# M66BoardSCH.net
KiCad netlist of a schematic drawn in Altium Designer
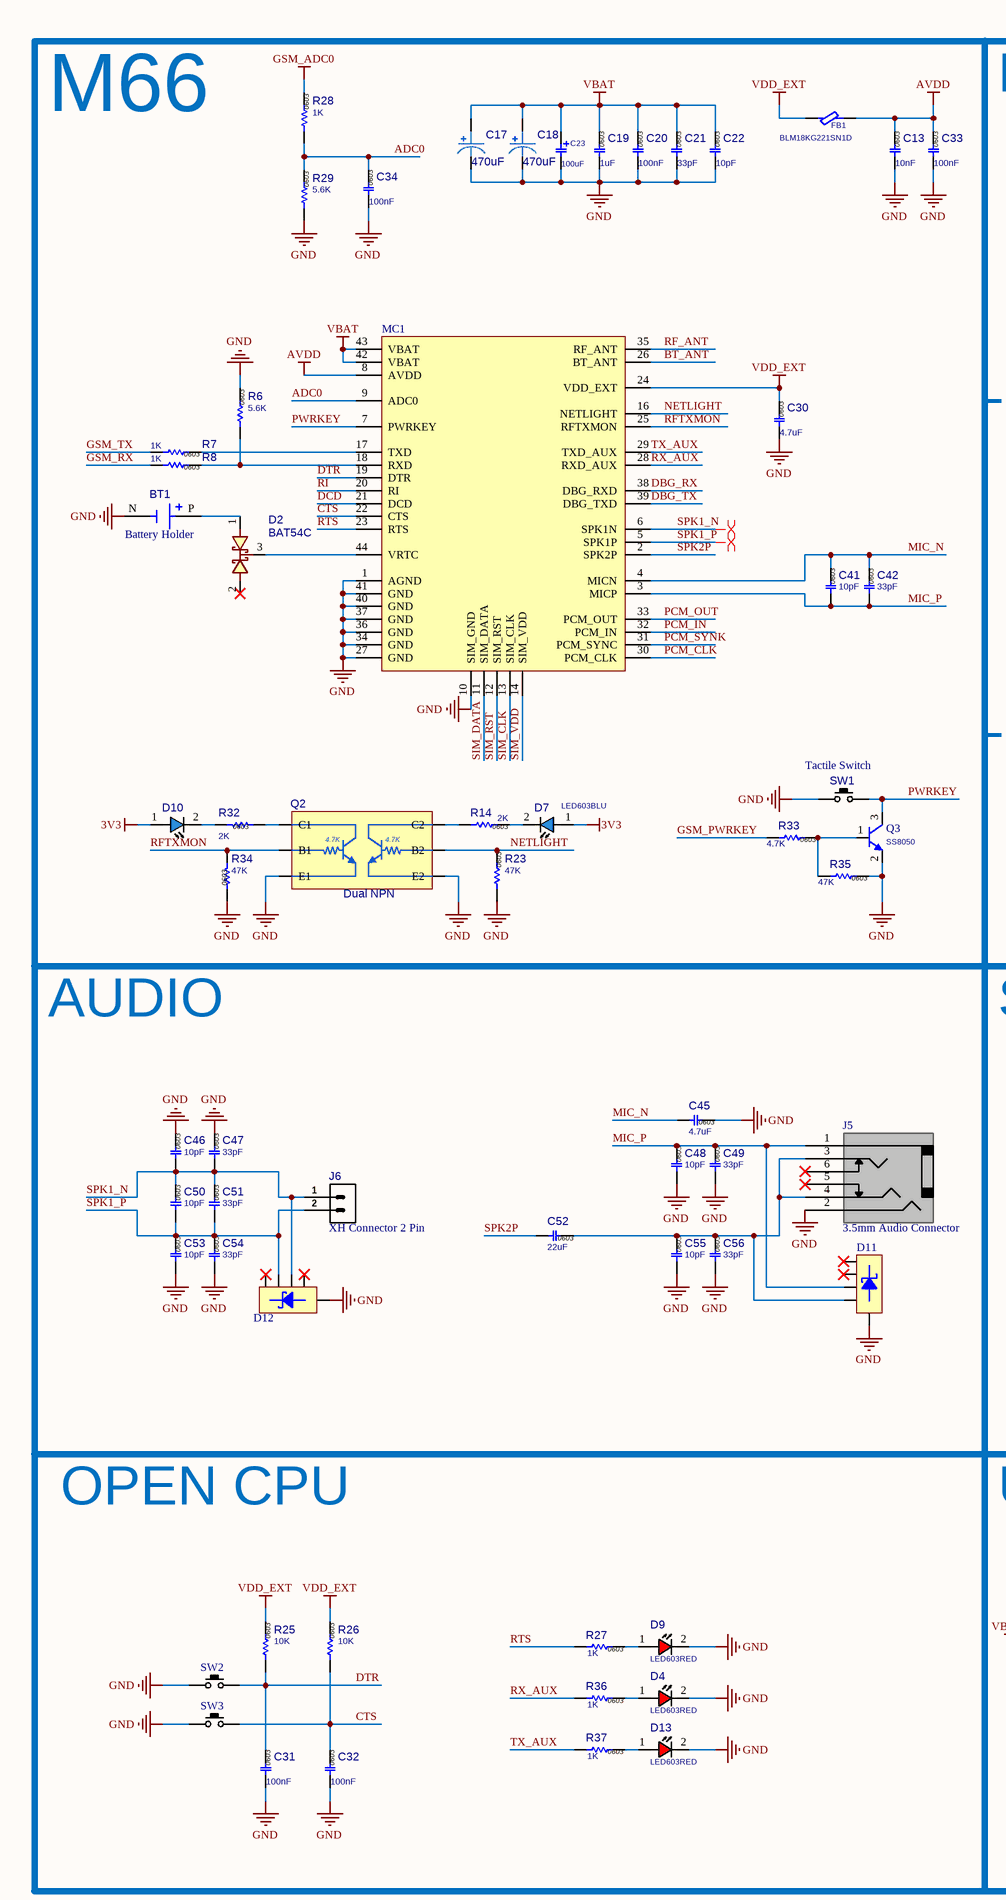
[diagram p0: M66BoardSCH.SchDoc, left]
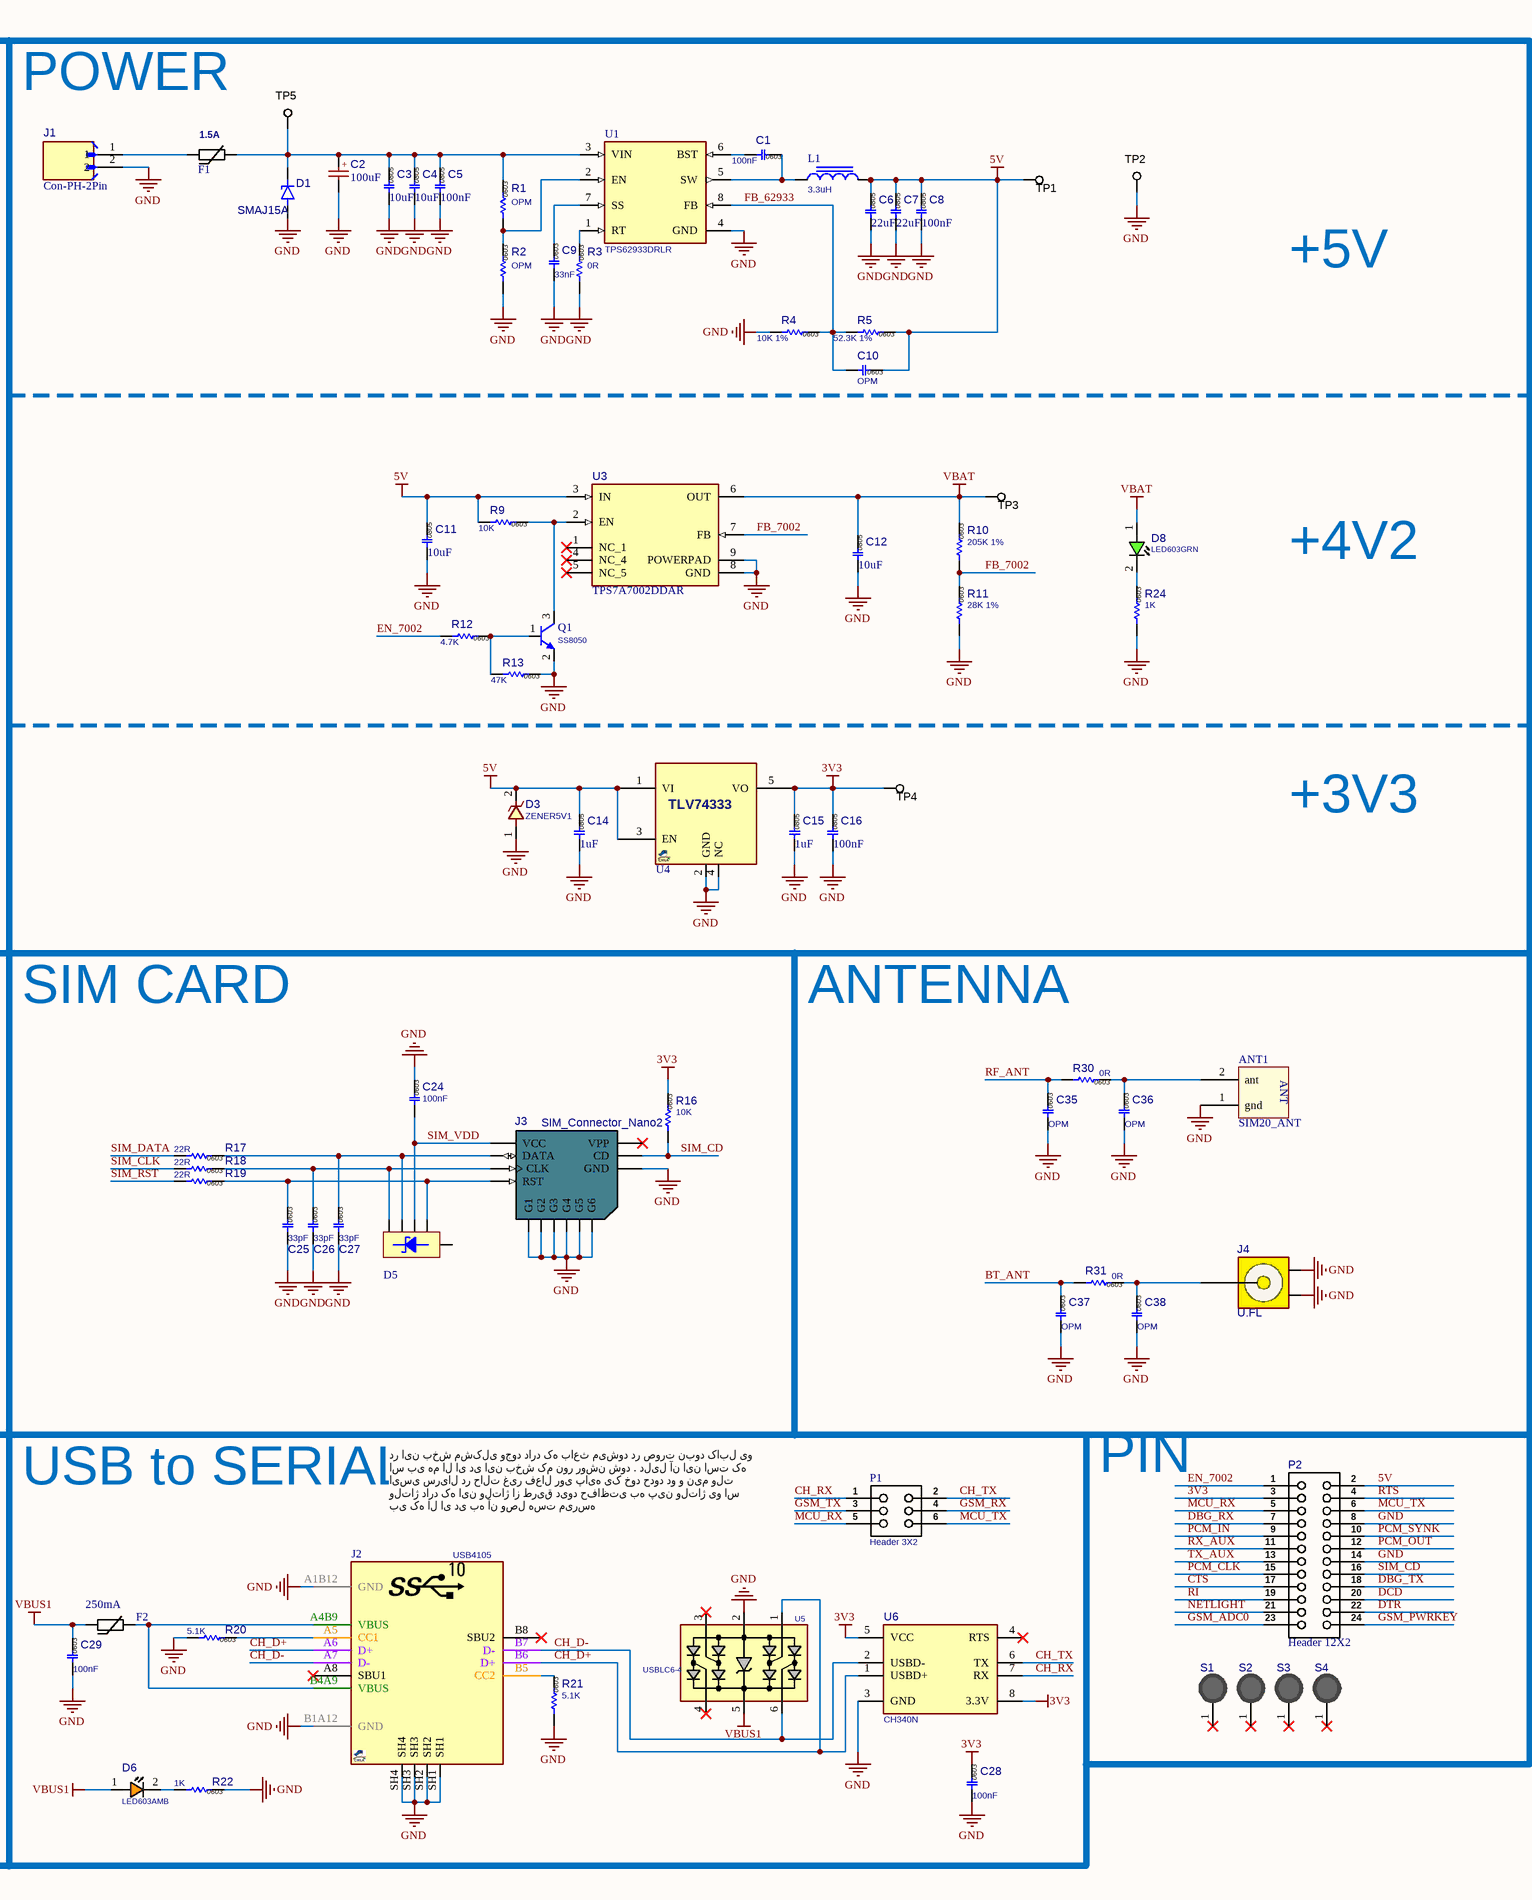
[diagram p1: M66BoardSCH.SchDoc, right]

(export (version "E")
  (design (tool "Eeschema 10.0.6"))
  (components
    (comp (ref "ANT1")
      (value "SIM20_ANT")
      (footprint "MY_SIM20_ANT")
      (description "ANT")
      (libsource (lib "AMINLIB") (part "SIM20_ANT"))
    )
    (comp (ref "BT1")
      (value "Battery Holder")
      (footprint "BS-06-B4AK008")
      (libsource (lib "Mehrdad") (part "Battery Holder"))
    )
    (comp (ref "C1")
      (value "100nF")
      (footprint "Cap SMD 0603")
      (libsource (lib "Mehrdad") (part "Cap SMD 0603"))
    )
    (comp (ref "C2")
      (value "100uF")
      (footprint "Cap SMD 6.3x5.4mm")
      (description "SMD Aluminum Electrolytic Capacitor")
      (fields
        (field (name "VOLTAGE") "12v")
        (field (name "TOLERANCE") "5%")
        (field (name "PUBLISHER") "Majid Derhambakhsh")
      )
      (libsource (lib "mBedLab Altium Library (2024-04-20)") (part "CAP Electrolytic SMD"))
    )
    (comp (ref "C3")
      (value "10uF")
      (footprint "Cap SMD 0805")
      (libsource (lib "Mehrdad") (part "Cap SMD 0805"))
    )
    (comp (ref "C4")
      (value "10uF")
      (footprint "Cap SMD 0805")
      (libsource (lib "Mehrdad") (part "Cap SMD 0805"))
    )
    (comp (ref "C5")
      (value "100nF")
      (footprint "Cap SMD 0805")
      (libsource (lib "Mehrdad") (part "Cap SMD 0805"))
    )
    (comp (ref "C6")
      (value "22uF")
      (footprint "Cap SMD 0805")
      (libsource (lib "Mehrdad") (part "Cap SMD 0805"))
    )
    (comp (ref "C7")
      (value "22uF")
      (footprint "Cap SMD 0805")
      (libsource (lib "Mehrdad") (part "Cap SMD 0805"))
    )
    (comp (ref "C8")
      (value "100nF")
      (footprint "Cap SMD 0805")
      (libsource (lib "Mehrdad") (part "Cap SMD 0805"))
    )
    (comp (ref "C9")
      (value "33nF")
      (footprint "Cap SMD 0603")
      (libsource (lib "Mehrdad") (part "Cap SMD 0603"))
    )
    (comp (ref "C10")
      (value "OPM")
      (footprint "Cap SMD 0603")
      (libsource (lib "Mehrdad") (part "Cap SMD 0603"))
    )
    (comp (ref "C11")
      (value "10uF")
      (footprint "Cap SMD 0805")
      (libsource (lib "Mehrdad") (part "Cap SMD 0805"))
    )
    (comp (ref "C12")
      (value "10uF")
      (footprint "Cap SMD 0805")
      (libsource (lib "Mehrdad") (part "Cap SMD 0805"))
    )
    (comp (ref "C13")
      (value "10nF")
      (footprint "Cap SMD 0603")
      (libsource (lib "Mehrdad") (part "Cap SMD 0603"))
    )
    (comp (ref "C14")
      (value "1uF")
      (footprint "Cap SMD 0805")
      (libsource (lib "Mehrdad") (part "Cap SMD 0805"))
    )
    (comp (ref "C15")
      (value "1uF")
      (footprint "Cap SMD 0805")
      (libsource (lib "Mehrdad") (part "Cap SMD 0805"))
    )
    (comp (ref "C16")
      (value "100nF")
      (footprint "Cap SMD 0805")
      (libsource (lib "Mehrdad") (part "Cap SMD 0805"))
    )
    (comp (ref "C17")
      (value "470uF")
      (footprint "Solid Capacitor 6.3x8mm")
      (description "Solid Polymer Electrolytic Capacitor")
      (libsource (lib "Mehrdad") (part "CAP Solid"))
    )
    (comp (ref "C18")
      (value "470uF")
      (footprint "Solid Capacitor 6.3x8mm")
      (description "Solid Polymer Electrolytic Capacitor")
      (libsource (lib "Mehrdad") (part "CAP Solid"))
    )
    (comp (ref "C19")
      (value "1uF")
      (footprint "Cap SMD 0603")
      (libsource (lib "Mehrdad") (part "Cap SMD 0603"))
    )
    (comp (ref "C20")
      (value "100nF")
      (footprint "Cap SMD 0603")
      (libsource (lib "Mehrdad") (part "Cap SMD 0603"))
    )
    (comp (ref "C21")
      (value "33pF")
      (footprint "Cap SMD 0603")
      (libsource (lib "Mehrdad") (part "Cap SMD 0603"))
    )
    (comp (ref "C22")
      (value "10pF")
      (footprint "Cap SMD 0603")
      (libsource (lib "Mehrdad") (part "Cap SMD 0603"))
    )
    (comp (ref "C23")
      (value "100uF")
      (footprint "C_TN_3528_BLK")
      (description "CAP, SMD, TAN")
      (fields (field (name "MANF") "VISHAY") (field (name "MANF_P#") "T55A106M6R3C0300"))
      (libsource (lib "AVR_RCS") (part "CAP_SMD_TAN_4"))
    )
    (comp (ref "C24")
      (value "100nF")
      (footprint "Cap SMD 0603")
      (libsource (lib "Mehrdad") (part "Cap SMD 0603"))
    )
    (comp (ref "C25")
      (value "33pF")
      (footprint "Cap SMD 0603")
      (libsource (lib "Mehrdad") (part "Cap SMD 0603"))
    )
    (comp (ref "C26")
      (value "33pF")
      (footprint "Cap SMD 0603")
      (libsource (lib "Mehrdad") (part "Cap SMD 0603"))
    )
    (comp (ref "C27")
      (value "33pF")
      (footprint "Cap SMD 0603")
      (libsource (lib "Mehrdad") (part "Cap SMD 0603"))
    )
    (comp (ref "C28")
      (value "100nF")
      (footprint "Cap SMD 0603")
      (libsource (lib "Mehrdad") (part "Cap SMD 0603"))
    )
    (comp (ref "C29")
      (value "100nF")
      (footprint "Cap SMD 0603")
      (libsource (lib "Mehrdad") (part "Cap SMD 0603"))
    )
    (comp (ref "C30")
      (value "4.7uF")
      (footprint "Cap SMD 0603")
      (libsource (lib "Mehrdad") (part "Cap SMD 0603"))
    )
    (comp (ref "C31")
      (value "100nF")
      (footprint "Cap SMD 0603")
      (libsource (lib "Mehrdad") (part "Cap SMD 0603"))
    )
    (comp (ref "C32")
      (value "100nF")
      (footprint "Cap SMD 0603")
      (libsource (lib "Mehrdad") (part "Cap SMD 0603"))
    )
    (comp (ref "C33")
      (value "100nF")
      (footprint "Cap SMD 0603")
      (libsource (lib "Mehrdad") (part "Cap SMD 0603"))
    )
    (comp (ref "C34")
      (value "100nF")
      (footprint "Cap SMD 0603")
      (libsource (lib "Mehrdad") (part "Cap SMD 0603"))
    )
    (comp (ref "C35")
      (value "OPM")
      (footprint "Cap SMD 0603")
      (libsource (lib "Mehrdad") (part "Cap SMD 0603"))
    )
    (comp (ref "C36")
      (value "OPM")
      (footprint "Cap SMD 0603")
      (libsource (lib "Mehrdad") (part "Cap SMD 0603"))
    )
    (comp (ref "C37")
      (value "OPM")
      (footprint "Cap SMD 0603")
      (libsource (lib "Mehrdad") (part "Cap SMD 0603"))
    )
    (comp (ref "C38")
      (value "OPM")
      (footprint "Cap SMD 0603")
      (libsource (lib "Mehrdad") (part "Cap SMD 0603"))
    )
    (comp (ref "C41")
      (value "10pF")
      (footprint "Cap SMD 0603")
      (libsource (lib "Mehrdad") (part "Cap SMD 0603"))
    )
    (comp (ref "C42")
      (value "33pF")
      (footprint "Cap SMD 0603")
      (libsource (lib "Mehrdad") (part "Cap SMD 0603"))
    )
    (comp (ref "C45")
      (value "4.7uF")
      (footprint "Cap SMD 0603")
      (libsource (lib "Mehrdad") (part "Cap SMD 0603"))
    )
    (comp (ref "C46")
      (value "10pF")
      (footprint "Cap SMD 0603")
      (libsource (lib "Mehrdad") (part "Cap SMD 0603"))
    )
    (comp (ref "C47")
      (value "33pF")
      (footprint "Cap SMD 0603")
      (libsource (lib "Mehrdad") (part "Cap SMD 0603"))
    )
    (comp (ref "C48")
      (value "10pF")
      (footprint "Cap SMD 0603")
      (libsource (lib "Mehrdad") (part "Cap SMD 0603"))
    )
    (comp (ref "C49")
      (value "33pF")
      (footprint "Cap SMD 0603")
      (libsource (lib "Mehrdad") (part "Cap SMD 0603"))
    )
    (comp (ref "C50")
      (value "10pF")
      (footprint "Cap SMD 0603")
      (libsource (lib "Mehrdad") (part "Cap SMD 0603"))
    )
    (comp (ref "C51")
      (value "33pF")
      (footprint "Cap SMD 0603")
      (libsource (lib "Mehrdad") (part "Cap SMD 0603"))
    )
    (comp (ref "C52")
      (value "22uF")
      (footprint "Cap SMD 0603")
      (libsource (lib "Mehrdad") (part "Cap SMD 0603"))
    )
    (comp (ref "C53")
      (value "10pF")
      (footprint "Cap SMD 0603")
      (libsource (lib "Mehrdad") (part "Cap SMD 0603"))
    )
    (comp (ref "C54")
      (value "33pF")
      (footprint "Cap SMD 0603")
      (libsource (lib "Mehrdad") (part "Cap SMD 0603"))
    )
    (comp (ref "C55")
      (value "10pF")
      (footprint "Cap SMD 0603")
      (libsource (lib "Mehrdad") (part "Cap SMD 0603"))
    )
    (comp (ref "C56")
      (value "33pF")
      (footprint "Cap SMD 0603")
      (libsource (lib "Mehrdad") (part "Cap SMD 0603"))
    )
    (comp (ref "D1")
      (value "SMAJ15A")
      (footprint "SMAJ15A")
      (description "TVS Diode Uni-directional 15V SMA  BR Voltage : 16.7V  Clamping Volatage : 24.4V")
      (libsource (lib "Mehrdad") (part "SMAJ15A"))
    )
    (comp (ref "D2")
      (value "BAT54C")
      (footprint "SOT23_3")
      (description "DIODE, SCHOTTKY, DUAL, 30V, 0.2A")
      (fields (field (name "MANF") "Diodes") (field (name "MANF_P#") "BAT54C-7-F"))
      (libsource (lib "diode") (part "DIODE_SMD_SCHOTTKY_BAT54C"))
    )
    (comp (ref "D3")
      (value "ZENER5V1")
      (footprint "D_SOD123W")
      (description "DIODE, ZENER, 1W, 5.1V")
      (fields (field (name "MANF") "Diodes") (field (name "MANF_P#") "BZT52HC5V1WF-7"))
      (libsource (lib "AVR_RCS") (part "DIODE_SMD_ZENER_BZT52HC5V1"))
    )
    (comp (ref "D4")
      (value "LED603RED")
      (footprint "LED0603RED")
      (description "LED, SMD, 0603, RED")
      (fields (field (name "MANF") "MANF") (field (name "MANF_P#") "MANF_PART#"))
      (libsource (lib "led(diode)") (part "LED_SMD_0603_RED"))
    )
    (comp (ref "D5")
      (value "SMF-05")
      (footprint "SC70-5_N")
      (description "TVS Diode Array")
      (fields (field (name "VALIDATION") "Valid"))
      (libsource (lib "") (part "Semi_Diod_TVS_SMF05_1"))
    )
    (comp (ref "D6")
      (value "LED603AMB")
      (footprint "LED0603AMB")
      (description "LED, SMD, 0603, AMBER, 606nm")
      (fields (field (name "MANF") "OSRAM") (field (name "MANF_P#") "L29K-H2K1-24-Z"))
      (libsource (lib "led(diode)") (part "LED_SMD_0603_AMB"))
    )
    (comp (ref "D7")
      (value "LED603BLU")
      (footprint "LED0603BLU")
      (description "LED, SMD, 0603, BLUE")
      (fields (field (name "MANF") "MANF") (field (name "MANF_P#") "MANF_PART#"))
      (libsource (lib "led(diode)") (part "LED_SMD_0603_BLU"))
    )
    (comp (ref "D8")
      (value "LED603GRN")
      (footprint "LED0603GRN")
      (description "LED, SMD, 0603, GREEN")
      (fields (field (name "MANF") "Kingbright") (field (name "MANF_P#") "APT1608SGC"))
      (libsource (lib "led(diode)") (part "LED_SMD_0603_GRN"))
    )
    (comp (ref "D9")
      (value "LED603RED")
      (footprint "LED0603RED")
      (description "LED, SMD, 0603, RED")
      (fields (field (name "MANF") "MANF") (field (name "MANF_P#") "MANF_PART#"))
      (libsource (lib "led(diode)") (part "LED_SMD_0603_RED"))
    )
    (comp (ref "D10")
      (value "LED603BLU")
      (footprint "LED0603BLU")
      (description "LED, SMD, 0603, BLUE")
      (fields (field (name "MANF") "MANF") (field (name "MANF_P#") "MANF_PART#"))
      (libsource (lib "led(diode)") (part "LED_SMD_0603_BLU"))
    )
    (comp (ref "D11")
      (value "SMF-05")
      (footprint "SC70-5_N")
      (description "TVS Diode Array")
      (fields (field (name "VALIDATION") "Valid"))
      (libsource (lib "aKaReZa") (part "Semi_Diod_TVS_SMF05"))
    )
    (comp (ref "D12")
      (value "SMF-05")
      (footprint "SC70-5_N")
      (description "TVS Diode Array")
      (fields (field (name "VALIDATION") "Valid"))
      (libsource (lib "") (part "Semi_Diod_TVS_SMF05_1"))
    )
    (comp (ref "D13")
      (value "LED603RED")
      (footprint "LED0603RED")
      (description "LED, SMD, 0603, RED")
      (fields (field (name "MANF") "MANF") (field (name "MANF_P#") "MANF_PART#"))
      (libsource (lib "led(diode)") (part "LED_SMD_0603_RED"))
    )
    (comp (ref "F1")
      (value "1.5A")
      (footprint "FUSE1206 (3216)")
      (fields (field (name "PUBLISHER") "Majid Derhambakhsh"))
      (libsource (lib "mBedLab Altium Library (2024-04-20)") (part "PPTC Resettable Fuses"))
    )
    (comp (ref "F2")
      (value "250mA")
      (footprint "FUSE0603 (1608)")
      (fields (field (name "PUBLISHER") "Majid Derhambakhsh"))
      (libsource (lib "mBedLab Altium Library (2024-04-20)") (part "PPTC Resettable Fuses"))
    )
    (comp (ref "FB1")
      (value "BLM18KG221SN1D")
      (footprint "L0603")
      (description "FERRITE_Bead, 0603, 2A, 50mOhm, 120@100MHz")
      (fields (field (name "MANF") "MURATA") (field (name "MANF_P#") "BLM18PG121SN1D"))
      (libsource (lib "emi_filter") (part "FBEAD_SMD_BLM18PG121"))
    )
    (comp (ref "J1")
      (value "Con-PH-2Pin")
      (footprint "Con-PH-2Pin-RA")
      (description "Connector Header Through Hole 2 position 0.079 (2.00mm)")
      (libsource (lib "Mehrdad") (part "Con-PH-2Pin"))
    )
    (comp (ref "J2")
      (value "USB4105")
      (footprint "USBC_SMD_16_USB4105")
      (description "CONN, USB, Type C, USB 2.0, Right-Angle, SMD")
      (fields (field (name "MANF") "GCT") (field (name "MANF_P#") "USB4105-GF-A"))
      (libsource (lib "conn_usbc") (part "CONN_USBC_SMD_16_USB4105"))
    )
    (comp (ref "J3")
      (value "SIM_Connector_Nano2")
      (footprint "SIM_Connector_Nano2")
      (description "Nano Sim Card 6P SMT-Card Detection")
      (libsource (lib "Mehrdad") (part "SIM_Connector_Nano2"))
    )
    (comp (ref "J4")
      (value "U.FL")
      (footprint "UFL")
      (description "CONN, RF, U.FL, STRAIGHT, Ultra Miniature Coaxial")
      (fields
        (field (name "MANF_P#") "CONUFL001-SMD, U.FL-R-SMT-1(10), 128-0711-201")
        (field (name "MANF") "Linx, Hirose, Cinch")
      )
      (libsource (lib "conn_rf") (part "CONN_RF_UFL"))
    )
    (comp (ref "J5")
      (value "3.5mm Audio Connector")
      (footprint "PJ311D")
      (libsource (lib "Mehrdad") (part "PJ311D"))
    )
    (comp (ref "J6")
      (value "XH Connector 2 Pin")
      (footprint "XH 2 Pin - 2.5mm")
      (description "XH, 2-Pin")
      (fields (field (name "PUBLISHER") "Majid Derhambakhsh"))
      (libsource (lib "mBedLab Altium Library (2024-04-20)") (part "XH 2"))
    )
    (comp (ref "L1")
      (value "3.3uH")
      (footprint "SMD Inductor 3")
      (description "1008 (2520 metric) Part Number : DFE252012F-4R7M=P2")
      (libsource (lib "Mehrdad") (part "SMD Inductor 3"))
    )
    (comp (ref "MC1")
      (value "M66")
      (footprint "m66")
      (description "Quectel GSM/GPRS Module")
      (fields (field (name "VALIDATION") "Valid"))
      (libsource (lib "AVR_RCS") (part "ModSen_Com_M66"))
    )
    (comp (ref "P1")
      (value "Header 3X2")
      (footprint "HDR 2X3 Male Top")
      (description "Header, 3-Pin, Dual row")
      (fields (field (name "PUBLISHER") "Majid Derhambakhsh"))
      (libsource (lib "mBedLab Altium Library (2024-04-20)") (part "Header 3X2"))
    )
    (comp (ref "P2")
      (value "Header 12X2")
      (footprint "HDR 2X12 Male Top")
      (description "Header, 12-Pin, Dual row")
      (fields (field (name "PUBLISHER") "Majid Derhambakhsh"))
      (libsource (lib "mBedLab Altium Library (2024-04-20)") (part "Header 12X2"))
    )
    (comp (ref "Q1")
      (value "SS8050")
      (footprint "SOT23_3")
      (description "BJT, NPN, 25v, 1.5A, SMD, SOT23")
      (fields (field (name "MANF") "GALAXY"))
      (libsource (lib "transistor_bjt") (part "NPN_SS8050_SOT23"))
    )
    (comp (ref "Q2")
      (value "Dual NPN")
      (footprint "PUMH7")
      (description "2 NPN 50V 100mA Transistors (Resistor-Equipped R1 = 4.7kΩ) SOT-363")
      (libsource (lib "Mehrdad") (part "PUMH7"))
    )
    (comp (ref "Q3")
      (value "SS8050")
      (footprint "SOT23_3")
      (description "BJT, NPN, 25v, 1.5A, SMD, SOT23")
      (fields (field (name "MANF") "GALAXY"))
      (libsource (lib "transistor_bjt") (part "NPN_SS8050_SOT23"))
    )
    (comp (ref "R1")
      (value "OPM")
      (footprint "Res SMD 0603")
      (libsource (lib "Mehrdad") (part "Res SMD 0603"))
    )
    (comp (ref "R2")
      (value "OPM")
      (footprint "Res SMD 0603")
      (libsource (lib "Mehrdad") (part "Res SMD 0603"))
    )
    (comp (ref "R3")
      (value "0R")
      (footprint "Res SMD 0603")
      (libsource (lib "Mehrdad") (part "Res SMD 0603"))
    )
    (comp (ref "R4")
      (value "10K 1%")
      (footprint "Res SMD 0603")
      (libsource (lib "Mehrdad") (part "Res SMD 0603"))
    )
    (comp (ref "R5")
      (value "52.3K 1%")
      (footprint "Res SMD 0603")
      (libsource (lib "Mehrdad") (part "Res SMD 0603"))
    )
    (comp (ref "R6")
      (value "5.6K")
      (footprint "Res SMD 0603")
      (libsource (lib "Mehrdad") (part "Res SMD 0603"))
    )
    (comp (ref "R7")
      (value "1K")
      (footprint "Res SMD 0603")
      (libsource (lib "Mehrdad") (part "Res SMD 0603"))
    )
    (comp (ref "R8")
      (value "1K")
      (footprint "Res SMD 0603")
      (libsource (lib "Mehrdad") (part "Res SMD 0603"))
    )
    (comp (ref "R9")
      (value "10K")
      (footprint "Res SMD 0603")
      (libsource (lib "Mehrdad") (part "Res SMD 0603"))
    )
    (comp (ref "R10")
      (value "205K 1%")
      (footprint "Res SMD 0603")
      (libsource (lib "Mehrdad") (part "Res SMD 0603"))
    )
    (comp (ref "R11")
      (value "28K 1%")
      (footprint "Res SMD 0603")
      (libsource (lib "Mehrdad") (part "Res SMD 0603"))
    )
    (comp (ref "R12")
      (value "4.7K")
      (footprint "Res SMD 0603")
      (libsource (lib "Mehrdad") (part "Res SMD 0603"))
    )
    (comp (ref "R13")
      (value "47K")
      (footprint "Res SMD 0603")
      (libsource (lib "Mehrdad") (part "Res SMD 0603"))
    )
    (comp (ref "R14")
      (value "2K")
      (footprint "Res SMD 0603")
      (libsource (lib "Mehrdad") (part "Res SMD 0603"))
    )
    (comp (ref "R16")
      (value "10K")
      (footprint "Res SMD 0603")
      (libsource (lib "Mehrdad") (part "Res SMD 0603"))
    )
    (comp (ref "R17")
      (value "22R")
      (footprint "Res SMD 0603")
      (libsource (lib "Mehrdad") (part "Res SMD 0603"))
    )
    (comp (ref "R18")
      (value "22R")
      (footprint "Res SMD 0603")
      (libsource (lib "Mehrdad") (part "Res SMD 0603"))
    )
    (comp (ref "R19")
      (value "22R")
      (footprint "Res SMD 0603")
      (libsource (lib "Mehrdad") (part "Res SMD 0603"))
    )
    (comp (ref "R20")
      (value "5.1K")
      (footprint "Res SMD 0603")
      (libsource (lib "Mehrdad") (part "Res SMD 0603"))
    )
    (comp (ref "R21")
      (value "5.1K")
      (footprint "Res SMD 0603")
      (libsource (lib "Mehrdad") (part "Res SMD 0603"))
    )
    (comp (ref "R22")
      (value "1K")
      (footprint "Res SMD 0603")
      (libsource (lib "Mehrdad") (part "Res SMD 0603"))
    )
    (comp (ref "R23")
      (value "47K")
      (footprint "Res SMD 0603")
      (libsource (lib "Mehrdad") (part "Res SMD 0603"))
    )
    (comp (ref "R24")
      (value "1K")
      (footprint "Res SMD 0603")
      (libsource (lib "Mehrdad") (part "Res SMD 0603"))
    )
    (comp (ref "R25")
      (value "10K")
      (footprint "Res SMD 0603")
      (libsource (lib "Mehrdad") (part "Res SMD 0603"))
    )
    (comp (ref "R26")
      (value "10K")
      (footprint "Res SMD 0603")
      (libsource (lib "Mehrdad") (part "Res SMD 0603"))
    )
    (comp (ref "R27")
      (value "1K")
      (footprint "Res SMD 0603")
      (libsource (lib "Mehrdad") (part "Res SMD 0603"))
    )
    (comp (ref "R28")
      (value "1K")
      (footprint "Res SMD 0603")
      (libsource (lib "Mehrdad") (part "Res SMD 0603"))
    )
    (comp (ref "R29")
      (value "5.6K")
      (footprint "Res SMD 0603")
      (libsource (lib "Mehrdad") (part "Res SMD 0603"))
    )
    (comp (ref "R30")
      (value "0R")
      (footprint "Res SMD 0603")
      (libsource (lib "Mehrdad") (part "Res SMD 0603"))
    )
    (comp (ref "R31")
      (value "0R")
      (footprint "Res SMD 0603")
      (libsource (lib "Mehrdad") (part "Res SMD 0603"))
    )
    (comp (ref "R32")
      (value "2K")
      (footprint "Res SMD 0603")
      (libsource (lib "Mehrdad") (part "Res SMD 0603"))
    )
    (comp (ref "R33")
      (value "4.7K")
      (footprint "Res SMD 0603")
      (libsource (lib "Mehrdad") (part "Res SMD 0603"))
    )
    (comp (ref "R34")
      (value "47K")
      (footprint "Res SMD 0603")
      (libsource (lib "Mehrdad") (part "Res SMD 0603"))
    )
    (comp (ref "R35")
      (value "47K")
      (footprint "Res SMD 0603")
      (libsource (lib "Mehrdad") (part "Res SMD 0603"))
    )
    (comp (ref "R36")
      (value "1K")
      (footprint "Res SMD 0603")
      (libsource (lib "Mehrdad") (part "Res SMD 0603"))
    )
    (comp (ref "R37")
      (value "1K")
      (footprint "Res SMD 0603")
      (libsource (lib "Mehrdad") (part "Res SMD 0603"))
    )
    (comp (ref "S1") (value "Screw 1") (footprint "Screw 1") (libsource (lib "Mehrdad") (part "Screw 1")))
    (comp (ref "S2") (value "Screw 1") (footprint "Screw 1") (libsource (lib "Mehrdad") (part "Screw 1")))
    (comp (ref "S3") (value "Screw 1") (footprint "Screw 1") (libsource (lib "Mehrdad") (part "Screw 1")))
    (comp (ref "S4") (value "Screw 1") (footprint "Screw 1") (libsource (lib "Mehrdad") (part "Screw 1")))
    (comp (ref "SW1")
      (value "Tactile Switch")
      (footprint "Tactil Switch 3*4*2")
      (description "3x6x5 mm - 2 Pin")
      (libsource (lib "Mehrdad") (part "Tactile Switch"))
    )
    (comp (ref "SW2")
      (value "Tactile Switch")
      (footprint "Tactile Switch")
      (description "3x6x5 mm - 2 Pin")
      (libsource (lib "Mehrdad") (part "Tactile Switch"))
    )
    (comp (ref "SW3")
      (value "Tactile Switch")
      (footprint "Tactile Switch")
      (description "3x6x5 mm - 2 Pin")
      (libsource (lib "Mehrdad") (part "Tactile Switch"))
    )
    (comp (ref "TP1")
      (value "TESTPOINT_SMD")
      (footprint "TPSMD_S1")
      (description "TEST POINT")
      (fields (field (name "MANF") "MANF") (field (name "MANF_P#") "MANF_P#"))
      (libsource (lib "test-tp_jumper") (part "TESTPOINT_SMD"))
    )
    (comp (ref "TP2")
      (value "TESTPOINT_SMD")
      (footprint "TPSMD_S1")
      (description "TEST POINT")
      (fields (field (name "MANF") "MANF") (field (name "MANF_P#") "MANF_P#"))
      (libsource (lib "test-tp_jumper") (part "TESTPOINT_SMD"))
    )
    (comp (ref "TP3")
      (value "TESTPOINT_SMD")
      (footprint "TPSMD_S1")
      (description "TEST POINT")
      (fields (field (name "MANF") "MANF") (field (name "MANF_P#") "MANF_P#"))
      (libsource (lib "test-tp_jumper") (part "TESTPOINT_SMD"))
    )
    (comp (ref "TP4")
      (value "TESTPOINT_SMD")
      (footprint "TPSMD_S1")
      (description "TEST POINT")
      (fields (field (name "MANF") "MANF") (field (name "MANF_P#") "MANF_P#"))
      (libsource (lib "test-tp_jumper") (part "TESTPOINT_SMD"))
    )
    (comp (ref "TP5")
      (value "TESTPOINT_SMD")
      (footprint "TPSMD_S1")
      (description "TEST POINT")
      (fields (field (name "MANF") "MANF") (field (name "MANF_P#") "MANF_P#"))
      (libsource (lib "test-tp_jumper") (part "TESTPOINT_SMD"))
    )
    (comp (ref "U1")
      (value "TPS62933DRLR")
      (footprint "TPS62933DRLR")
      (description "3.8-V to 30-V, 3-A, 200-kHz to 2.2-MHz, low-IQ synchronous buck converter in SOT-583 package")
      (libsource (lib "Mehrdad") (part "TPS62933DRLR"))
    )
    (comp (ref "U3")
      (value "TPS7A7002DDAR")
      (footprint "TPS7A7002DDAR")
      (libsource (lib "Mehrdad") (part "TPS7A7002DDAR"))
    )
    (comp (ref "U4")
      (value "TLV74333")
      (footprint "SOT23_5")
      (description "REG, Linear, LDO0.12V, Fixed, 300mA, VIN1.4~5.5V, VOUT1~5.5V, SOT-23-5")
      (fields (field (name "MANF") "Texas Instruments") (field (name "MANF_P#") "TLV74333PDQN"))
      (libsource (lib "pwr_reg_linear_LDO_highPSRR") (part "VREG_TLV74333_SOT23"))
    )
    (comp (ref "U5")
      (value "USBLC6-4")
      (footprint "SOT23_6")
      (description "TVS, ESD PROTECT, 4CH")
      (fields (field (name "MANF_P#") "USBLC6-4SC6") (field (name "MANF") "ST"))
      (libsource (lib "protect_tvs_esd_fuse") (part "TVS_X4_USBLC6-4SC6"))
    )
    (comp (ref "U6")
      (value "CH340N")
      (footprint "SO8_narrow_N")
      (description "TTL To USB Chip")
      (fields (field (name "VALIDATION") "Valid"))
      (libsource (lib "aKaReZa") (part "IC_Converter_CH340N"))
    )
  )
  (nets
    (net (code "1") (name "/ADC0") (class "Default")
      (node (ref "C34") (pin "2") (pinfunction "2_2") (pintype "passive"))
      (node (ref "MC1") (pin "9") (pinfunction "ADC0_9") (pintype "passive"))
      (node (ref "R28") (pin "1") (pinfunction "1_1") (pintype "passive"))
      (node (ref "R29") (pin "2") (pinfunction "2_2") (pintype "passive"))
    )
    (net (code "2") (name "/BT_ANT") (class "Default")
      (node (ref "C37") (pin "2") (pinfunction "2_2") (pintype "passive"))
      (node (ref "MC1") (pin "26") (pinfunction "BT_ANT_26") (pintype "passive"))
      (node (ref "R31") (pin "1") (pinfunction "1_1") (pintype "passive"))
    )
    (net (code "3") (name "/CH_D+") (class "Default")
      (node (ref "J2") (pin "A6") (pinfunction "D+_A6") (pintype "passive"))
      (node (ref "J2") (pin "B6") (pinfunction "D+_B6") (pintype "passive"))
      (node (ref "U5") (pin "1") (pinfunction "1_1") (pintype "passive"))
      (node (ref "U6") (pin "1") (pinfunction "USBD+_1") (pintype "passive"))
    )
    (net (code "4") (name "/CH_D-") (class "Default")
      (node (ref "J2") (pin "A7") (pinfunction "D-_A7") (pintype "passive"))
      (node (ref "J2") (pin "B7") (pinfunction "D-_B7") (pintype "passive"))
      (node (ref "U5") (pin "6") (pinfunction "6_6") (pintype "passive"))
      (node (ref "U6") (pin "2") (pinfunction "USBD-_2") (pintype "passive"))
    )
    (net (code "5") (name "/CH_RX") (class "Default")
      (node (ref "P1") (pin "1") (pinfunction "1_1") (pintype "passive"))
      (node (ref "U6") (pin "7") (pinfunction "RX_7") (pintype "passive"))
    )
    (net (code "6") (name "/CH_TX") (class "Default")
      (node (ref "P1") (pin "2") (pinfunction "2_2") (pintype "passive"))
      (node (ref "U6") (pin "6") (pinfunction "TX_6") (pintype "passive"))
    )
    (net (code "7") (name "/CTS") (class "Default")
      (node (ref "C32") (pin "2") (pinfunction "2_2") (pintype "passive"))
      (node (ref "MC1") (pin "22") (pinfunction "CTS_22") (pintype "passive"))
      (node (ref "P2") (pin "17") (pinfunction "17_17") (pintype "passive"))
      (node (ref "R26") (pin "1") (pinfunction "1_1") (pintype "passive"))
      (node (ref "SW3") (pin "2") (pinfunction "P3_2") (pintype "passive"))
    )
    (net (code "8") (name "/DBG_RX") (class "Default")
      (node (ref "MC1") (pin "38") (pinfunction "DBG_RXD_38") (pintype "passive"))
      (node (ref "P2") (pin "7") (pinfunction "7_7") (pintype "passive"))
    )
    (net (code "9") (name "/DBG_TX") (class "Default")
      (node (ref "MC1") (pin "39") (pinfunction "DBG_TXD_39") (pintype "passive"))
      (node (ref "P2") (pin "18") (pinfunction "18_18") (pintype "passive"))
    )
    (net (code "10") (name "/DCD") (class "Default")
      (node (ref "MC1") (pin "21") (pinfunction "DCD_21") (pintype "passive"))
      (node (ref "P2") (pin "20") (pinfunction "20_20") (pintype "passive"))
    )
    (net (code "11") (name "/DTR") (class "Default")
      (node (ref "C31") (pin "2") (pinfunction "2_2") (pintype "passive"))
      (node (ref "MC1") (pin "19") (pinfunction "DTR_19") (pintype "passive"))
      (node (ref "P2") (pin "22") (pinfunction "22_22") (pintype "passive"))
      (node (ref "R25") (pin "1") (pinfunction "1_1") (pintype "passive"))
      (node (ref "SW2") (pin "2") (pinfunction "P3_2") (pintype "passive"))
    )
    (net (code "12") (name "/EN_7002") (class "Default")
      (node (ref "P2") (pin "1") (pinfunction "1_1") (pintype "passive"))
      (node (ref "R12") (pin "1") (pinfunction "1_1") (pintype "passive"))
    )
    (net (code "13") (name "/FB_7002") (class "Default")
      (node (ref "R10") (pin "1") (pinfunction "1_1") (pintype "passive"))
      (node (ref "R11") (pin "2") (pinfunction "2_2") (pintype "passive"))
      (node (ref "U3") (pin "7") (pinfunction "FB_7") (pintype "input"))
    )
    (net (code "14") (name "/FB_62933") (class "Default")
      (node (ref "C10") (pin "1") (pinfunction "1_1") (pintype "passive"))
      (node (ref "R4") (pin "2") (pinfunction "2_2") (pintype "passive"))
      (node (ref "R5") (pin "1") (pinfunction "1_1") (pintype "passive"))
      (node (ref "U1") (pin "8") (pinfunction "FB_8") (pintype "input"))
    )
    (net (code "15") (name "/GSM_PWRKEY") (class "Default")
      (node (ref "P2") (pin "24") (pinfunction "24_24") (pintype "passive"))
      (node (ref "R33") (pin "1") (pinfunction "1_1") (pintype "passive"))
    )
    (net (code "16") (name "/GSM_RX") (class "Default")
      (node (ref "P1") (pin "4") (pinfunction "4_4") (pintype "passive"))
      (node (ref "R8") (pin "1") (pinfunction "1_1") (pintype "passive"))
    )
    (net (code "17") (name "/GSM_TX") (class "Default")
      (node (ref "P1") (pin "3") (pinfunction "3_3") (pintype "passive"))
      (node (ref "R7") (pin "1") (pinfunction "1_1") (pintype "passive"))
    )
    (net (code "18") (name "/MCU_RX") (class "Default")
      (node (ref "P1") (pin "5") (pinfunction "5_5") (pintype "passive"))
      (node (ref "P2") (pin "5") (pinfunction "5_5") (pintype "passive"))
    )
    (net (code "19") (name "/MCU_TX") (class "Default")
      (node (ref "P1") (pin "6") (pinfunction "6_6") (pintype "passive"))
      (node (ref "P2") (pin "6") (pinfunction "6_6") (pintype "passive"))
    )
    (net (code "20") (name "/MIC_N") (class "Default")
      (node (ref "C41") (pin "2") (pinfunction "2_2") (pintype "passive"))
      (node (ref "C42") (pin "2") (pinfunction "2_2") (pintype "passive"))
      (node (ref "C45") (pin "1") (pinfunction "1_1") (pintype "passive"))
      (node (ref "MC1") (pin "4") (pinfunction "MICN_4") (pintype "passive"))
    )
    (net (code "21") (name "/MIC_P") (class "Default")
      (node (ref "C41") (pin "1") (pinfunction "1_1") (pintype "passive"))
      (node (ref "C42") (pin "1") (pinfunction "1_1") (pintype "passive"))
      (node (ref "C48") (pin "2") (pinfunction "2_2") (pintype "passive"))
      (node (ref "C49") (pin "2") (pinfunction "2_2") (pintype "passive"))
      (node (ref "D11") (pin "4") (pinfunction "K_4") (pintype "passive"))
      (node (ref "J5") (pin "1") (pinfunction "MIC_1") (pintype "passive"))
      (node (ref "MC1") (pin "3") (pinfunction "MICP_3") (pintype "passive"))
    )
    (net (code "22") (name "/NETLIGHT") (class "Default")
      (node (ref "MC1") (pin "16") (pinfunction "NETLIGHT_16") (pintype "passive"))
      (node (ref "P2") (pin "21") (pinfunction "21_21") (pintype "passive"))
      (node (ref "Q2") (pin "5") (pinfunction "B2_5") (pintype "power_in"))
      (node (ref "R23") (pin "2") (pinfunction "2_2") (pintype "passive"))
    )
    (net (code "23") (name "/PCM_CLK") (class "Default")
      (node (ref "MC1") (pin "30") (pinfunction "PCM_CLK_30") (pintype "passive"))
      (node (ref "P2") (pin "15") (pinfunction "15_15") (pintype "passive"))
    )
    (net (code "24") (name "/PCM_IN") (class "Default")
      (node (ref "MC1") (pin "32") (pinfunction "PCM_IN_32") (pintype "passive"))
      (node (ref "P2") (pin "9") (pinfunction "9_9") (pintype "passive"))
    )
    (net (code "25") (name "/PCM_OUT") (class "Default")
      (node (ref "MC1") (pin "33") (pinfunction "PCM_OUT_33") (pintype "passive"))
      (node (ref "P2") (pin "12") (pinfunction "12_12") (pintype "passive"))
    )
    (net (code "26") (name "/PCM_SYNK") (class "Default")
      (node (ref "MC1") (pin "31") (pinfunction "PCM_SYNC_31") (pintype "passive"))
      (node (ref "P2") (pin "10") (pinfunction "10_10") (pintype "passive"))
    )
    (net (code "27") (name "/PWRKEY") (class "Default")
      (node (ref "MC1") (pin "7") (pinfunction "PWRKEY_7") (pintype "passive"))
      (node (ref "Q3") (pin "3") (pinfunction "C_3") (pintype "passive"))
      (node (ref "SW1") (pin "2") (pinfunction "P3_2") (pintype "passive"))
    )
    (net (code "28") (name "/RFTXMON") (class "Default")
      (node (ref "MC1") (pin "25") (pinfunction "RFTXMON_25") (pintype "passive"))
      (node (ref "Q2") (pin "2") (pinfunction "B1_2") (pintype "power_in"))
      (node (ref "R34") (pin "2") (pinfunction "2_2") (pintype "passive"))
    )
    (net (code "29") (name "/RF_ANT") (class "Default")
      (node (ref "C35") (pin "2") (pinfunction "2_2") (pintype "passive"))
      (node (ref "MC1") (pin "35") (pinfunction "RF_ANT_35") (pintype "passive"))
      (node (ref "R30") (pin "1") (pinfunction "1_1") (pintype "passive"))
    )
    (net (code "30") (name "/RI") (class "Default")
      (node (ref "MC1") (pin "20") (pinfunction "RI_20") (pintype "passive"))
      (node (ref "P2") (pin "19") (pinfunction "19_19") (pintype "passive"))
    )
    (net (code "31") (name "/RTS") (class "Default")
      (node (ref "MC1") (pin "23") (pinfunction "RTS_23") (pintype "passive"))
      (node (ref "P2") (pin "4") (pinfunction "4_4") (pintype "passive"))
      (node (ref "R27") (pin "1") (pinfunction "1_1") (pintype "passive"))
    )
    (net (code "32") (name "/RX_AUX") (class "Default")
      (node (ref "MC1") (pin "28") (pinfunction "RXD_AUX_28") (pintype "passive"))
      (node (ref "P2") (pin "11") (pinfunction "11_11") (pintype "passive"))
      (node (ref "R36") (pin "1") (pinfunction "1_1") (pintype "passive"))
    )
    (net (code "33") (name "/SIM_CD") (class "Default")
      (node (ref "J3") (pin "CD") (pinfunction "CD_CD") (pintype "open_collector"))
      (node (ref "P2") (pin "16") (pinfunction "16_16") (pintype "passive"))
      (node (ref "R16") (pin "1") (pinfunction "1_1") (pintype "passive"))
    )
    (net (code "34") (name "/SIM_CLK") (class "Default")
      (node (ref "MC1") (pin "13") (pinfunction "SIM_CLK_13") (pintype "passive"))
      (node (ref "R18") (pin "1") (pinfunction "1_1") (pintype "passive"))
    )
    (net (code "35") (name "/SIM_DATA") (class "Default")
      (node (ref "MC1") (pin "11") (pinfunction "SIM_DATA_11") (pintype "passive"))
      (node (ref "R17") (pin "1") (pinfunction "1_1") (pintype "passive"))
    )
    (net (code "36") (name "/SIM_RST") (class "Default")
      (node (ref "MC1") (pin "12") (pinfunction "SIM_RST_12") (pintype "passive"))
      (node (ref "R19") (pin "1") (pinfunction "1_1") (pintype "passive"))
    )
    (net (code "37") (name "/SIM_VDD") (class "Default")
      (node (ref "C24") (pin "1") (pinfunction "1_1") (pintype "passive"))
      (node (ref "D5") (pin "4") (pinfunction "K_4") (pintype "passive"))
      (node (ref "J3") (pin "C1") (pinfunction "VCC_C1") (pintype "power_in"))
      (node (ref "MC1") (pin "14") (pinfunction "SIM_VDD_14") (pintype "passive"))
    )
    (net (code "38") (name "/SPK1_N") (class "Default")
      (node (ref "C46") (pin "1") (pinfunction "1_1") (pintype "passive"))
      (node (ref "C47") (pin "1") (pinfunction "1_1") (pintype "passive"))
      (node (ref "C50") (pin "2") (pinfunction "2_2") (pintype "passive"))
      (node (ref "C51") (pin "2") (pinfunction "2_2") (pintype "passive"))
      (node (ref "D12") (pin "4") (pinfunction "K_4") (pintype "passive"))
      (node (ref "J6") (pin "1") (pinfunction "1_1") (pintype "passive"))
      (node (ref "MC1") (pin "6") (pinfunction "SPK1N_6") (pintype "passive"))
    )
    (net (code "39") (name "/SPK1_P") (class "Default")
      (node (ref "C50") (pin "1") (pinfunction "1_1") (pintype "passive"))
      (node (ref "C51") (pin "1") (pinfunction "1_1") (pintype "passive"))
      (node (ref "C53") (pin "2") (pinfunction "2_2") (pintype "passive"))
      (node (ref "C54") (pin "2") (pinfunction "2_2") (pintype "passive"))
      (node (ref "D12") (pin "3") (pinfunction "K_3") (pintype "passive"))
      (node (ref "J6") (pin "2") (pinfunction "2_2") (pintype "passive"))
      (node (ref "MC1") (pin "5") (pinfunction "SPK1P_5") (pintype "passive"))
    )
    (net (code "40") (name "/SPK2P") (class "Default")
      (node (ref "C52") (pin "1") (pinfunction "1_1") (pintype "passive"))
      (node (ref "MC1") (pin "2") (pinfunction "SPK2P_2") (pintype "passive"))
    )
    (net (code "41") (name "/TX_AUX") (class "Default")
      (node (ref "MC1") (pin "29") (pinfunction "TXD_AUX_29") (pintype "passive"))
      (node (ref "P2") (pin "13") (pinfunction "13_13") (pintype "passive"))
      (node (ref "R37") (pin "1") (pinfunction "1_1") (pintype "passive"))
    )
    (net (code "42") (name "3V3") (class "Default")
      (node (ref "C15") (pin "2") (pinfunction "2_2") (pintype "passive"))
      (node (ref "C16") (pin "2") (pinfunction "2_2") (pintype "passive"))
      (node (ref "C28") (pin "2") (pinfunction "2_2") (pintype "passive"))
      (node (ref "D10") (pin "1") (pinfunction "ANODE_1") (pintype "passive"))
      (node (ref "D7") (pin "1") (pinfunction "ANODE_1") (pintype "passive"))
      (node (ref "P2") (pin "3") (pinfunction "3_3") (pintype "passive"))
      (node (ref "R16") (pin "2") (pinfunction "2_2") (pintype "passive"))
      (node (ref "TP4") (pin "1") (pinfunction "1_1") (pintype "passive"))
      (node (ref "U4") (pin "5") (pinfunction "VO_5") (pintype "passive"))
      (node (ref "U6") (pin "5") (pinfunction "VCC_5") (pintype "passive"))
      (node (ref "U6") (pin "8") (pinfunction "3.3V_8") (pintype "passive"))
    )
    (net (code "43") (name "5V") (class "Default")
      (node (ref "C10") (pin "2") (pinfunction "2_2") (pintype "passive"))
      (node (ref "C11") (pin "2") (pinfunction "2_2") (pintype "passive"))
      (node (ref "C14") (pin "2") (pinfunction "2_2") (pintype "passive"))
      (node (ref "C6") (pin "2") (pinfunction "2_2") (pintype "passive"))
      (node (ref "C7") (pin "2") (pinfunction "2_2") (pintype "passive"))
      (node (ref "C8") (pin "2") (pinfunction "2_2") (pintype "passive"))
      (node (ref "D3") (pin "2") (pinfunction "2_2") (pintype "passive"))
      (node (ref "L1") (pin "2") (pinfunction "2_2") (pintype "passive"))
      (node (ref "P2") (pin "2") (pinfunction "2_2") (pintype "passive"))
      (node (ref "R5") (pin "2") (pinfunction "2_2") (pintype "passive"))
      (node (ref "R9") (pin "1") (pinfunction "1_1") (pintype "passive"))
      (node (ref "TP1") (pin "1") (pinfunction "1_1") (pintype "passive"))
      (node (ref "U3") (pin "3") (pinfunction "IN_3") (pintype "input"))
      (node (ref "U4") (pin "1") (pinfunction "VI_1") (pintype "passive"))
      (node (ref "U4") (pin "3") (pinfunction "EN_3") (pintype "passive"))
    )
    (net (code "44") (name "AVDD") (class "Default")
      (node (ref "C13") (pin "2") (pinfunction "2_2") (pintype "passive"))
      (node (ref "C33") (pin "2") (pinfunction "2_2") (pintype "passive"))
      (node (ref "FB1") (pin "2") (pinfunction "2_2") (pintype "passive"))
      (node (ref "MC1") (pin "8") (pinfunction "AVDD_8") (pintype "passive"))
    )
    (net (code "45") (name "GND") (class "Default")
      (node (ref "ANT1") (pin "1") (pinfunction "gnd_1") (pintype "passive"))
      (node (ref "BT1") (pin "N") (pinfunction "NEG_N") (pintype "passive"))
      (node (ref "C11") (pin "1") (pinfunction "1_1") (pintype "passive"))
      (node (ref "C12") (pin "1") (pinfunction "1_1") (pintype "passive"))
      (node (ref "C13") (pin "1") (pinfunction "1_1") (pintype "passive"))
      (node (ref "C14") (pin "1") (pinfunction "1_1") (pintype "passive"))
      (node (ref "C15") (pin "1") (pinfunction "1_1") (pintype "passive"))
      (node (ref "C16") (pin "1") (pinfunction "1_1") (pintype "passive"))
      (node (ref "C17") (pin "2") (pinfunction "N_2") (pintype "power_in"))
      (node (ref "C18") (pin "2") (pinfunction "N_2") (pintype "power_in"))
      (node (ref "C19") (pin "1") (pinfunction "1_1") (pintype "passive"))
      (node (ref "C2") (pin "2") (pinfunction "-_2") (pintype "passive"))
      (node (ref "C20") (pin "1") (pinfunction "1_1") (pintype "passive"))
      (node (ref "C21") (pin "1") (pinfunction "1_1") (pintype "passive"))
      (node (ref "C22") (pin "1") (pinfunction "1_1") (pintype "passive"))
      (node (ref "C23") (pin "2") (pinfunction "2_2") (pintype "passive"))
      (node (ref "C24") (pin "2") (pinfunction "2_2") (pintype "passive"))
      (node (ref "C25") (pin "1") (pinfunction "1_1") (pintype "passive"))
      (node (ref "C26") (pin "1") (pinfunction "1_1") (pintype "passive"))
      (node (ref "C27") (pin "1") (pinfunction "1_1") (pintype "passive"))
      (node (ref "C28") (pin "1") (pinfunction "1_1") (pintype "passive"))
      (node (ref "C29") (pin "1") (pinfunction "1_1") (pintype "passive"))
      (node (ref "C3") (pin "1") (pinfunction "1_1") (pintype "passive"))
      (node (ref "C30") (pin "1") (pinfunction "1_1") (pintype "passive"))
      (node (ref "C31") (pin "1") (pinfunction "1_1") (pintype "passive"))
      (node (ref "C32") (pin "1") (pinfunction "1_1") (pintype "passive"))
      (node (ref "C33") (pin "1") (pinfunction "1_1") (pintype "passive"))
      (node (ref "C34") (pin "1") (pinfunction "1_1") (pintype "passive"))
      (node (ref "C35") (pin "1") (pinfunction "1_1") (pintype "passive"))
      (node (ref "C36") (pin "1") (pinfunction "1_1") (pintype "passive"))
      (node (ref "C37") (pin "1") (pinfunction "1_1") (pintype "passive"))
      (node (ref "C38") (pin "1") (pinfunction "1_1") (pintype "passive"))
      (node (ref "C4") (pin "1") (pinfunction "1_1") (pintype "passive"))
      (node (ref "C45") (pin "2") (pinfunction "2_2") (pintype "passive"))
      (node (ref "C46") (pin "2") (pinfunction "2_2") (pintype "passive"))
      (node (ref "C47") (pin "2") (pinfunction "2_2") (pintype "passive"))
      (node (ref "C48") (pin "1") (pinfunction "1_1") (pintype "passive"))
      (node (ref "C49") (pin "1") (pinfunction "1_1") (pintype "passive"))
      (node (ref "C5") (pin "1") (pinfunction "1_1") (pintype "passive"))
      (node (ref "C53") (pin "1") (pinfunction "1_1") (pintype "passive"))
      (node (ref "C54") (pin "1") (pinfunction "1_1") (pintype "passive"))
      (node (ref "C55") (pin "1") (pinfunction "1_1") (pintype "passive"))
      (node (ref "C56") (pin "1") (pinfunction "1_1") (pintype "passive"))
      (node (ref "C6") (pin "1") (pinfunction "1_1") (pintype "passive"))
      (node (ref "C7") (pin "1") (pinfunction "1_1") (pintype "passive"))
      (node (ref "C8") (pin "1") (pinfunction "1_1") (pintype "passive"))
      (node (ref "C9") (pin "1") (pinfunction "1_1") (pintype "passive"))
      (node (ref "D1") (pin "A") (pinfunction "A_A") (pintype "passive"))
      (node (ref "D11") (pin "2") (pinfunction "K_2") (pintype "passive"))
      (node (ref "D12") (pin "2") (pinfunction "K_2") (pintype "passive"))
      (node (ref "D13") (pin "2") (pinfunction "CATHODE_2") (pintype "passive"))
      (node (ref "D3") (pin "1") (pinfunction "1_1") (pintype "passive"))
      (node (ref "D4") (pin "2") (pinfunction "CATHODE_2") (pintype "passive"))
      (node (ref "D9") (pin "2") (pinfunction "CATHODE_2") (pintype "passive"))
      (node (ref "J1") (pin "2") (pinfunction "2_2") (pintype "passive"))
      (node (ref "J2") (pin "A1B12") (pinfunction "GND_A1B12") (pintype "passive"))
      (node (ref "J2") (pin "B1A12") (pinfunction "GND_B1A12") (pintype "passive"))
      (node (ref "J2") (pin "SH1") (pinfunction "SH1_SH1") (pintype "passive"))
      (node (ref "J2") (pin "SH2") (pinfunction "SH2_SH2") (pintype "passive"))
      (node (ref "J2") (pin "SH3") (pinfunction "SH3_SH3") (pintype "passive"))
      (node (ref "J2") (pin "SH4") (pinfunction "SH4_SH4") (pintype "passive"))
      (node (ref "J3") (pin "C5") (pinfunction "GND_C5") (pintype "power_in"))
      (node (ref "J3") (pin "G1") (pinfunction "G1_G1") (pintype "power_in"))
      (node (ref "J3") (pin "G2") (pinfunction "G2_G2") (pintype "power_in"))
      (node (ref "J3") (pin "G3") (pinfunction "G3_G3") (pintype "power_in"))
      (node (ref "J3") (pin "G4") (pinfunction "G4_G4") (pintype "power_in"))
      (node (ref "J3") (pin "G5") (pinfunction "G5_G5") (pintype "power_in"))
      (node (ref "J3") (pin "G6") (pinfunction "G6_G6") (pintype "power_in"))
      (node (ref "J4") (pin "2") (pinfunction "G1_2") (pintype "passive"))
      (node (ref "J4") (pin "3") (pinfunction "G2_3") (pintype "passive"))
      (node (ref "J5") (pin "2") (pinfunction "GND_2") (pintype "passive"))
      (node (ref "MC1") (pin "1") (pinfunction "AGND_1") (pintype "passive"))
      (node (ref "MC1") (pin "10") (pinfunction "SIM_GND_10") (pintype "passive"))
      (node (ref "MC1") (pin "27") (pinfunction "GND_27") (pintype "passive"))
      (node (ref "MC1") (pin "34") (pinfunction "GND_34") (pintype "passive"))
      (node (ref "MC1") (pin "36") (pinfunction "GND_36") (pintype "passive"))
      (node (ref "MC1") (pin "37") (pinfunction "GND_37") (pintype "passive"))
      (node (ref "MC1") (pin "40") (pinfunction "GND_40") (pintype "passive"))
      (node (ref "MC1") (pin "41") (pinfunction "GND_41") (pintype "passive"))
      (node (ref "P2") (pin "14") (pinfunction "14_14") (pintype "passive"))
      (node (ref "P2") (pin "8") (pinfunction "8_8") (pintype "passive"))
      (node (ref "Q1") (pin "2") (pinfunction "E_2") (pintype "passive"))
      (node (ref "Q2") (pin "1") (pinfunction "E1_1") (pintype "power_in"))
      (node (ref "Q2") (pin "4") (pinfunction "E2_4") (pintype "power_in"))
      (node (ref "Q3") (pin "2") (pinfunction "E_2") (pintype "passive"))
      (node (ref "R11") (pin "1") (pinfunction "1_1") (pintype "passive"))
      (node (ref "R13") (pin "2") (pinfunction "2_2") (pintype "passive"))
      (node (ref "R2") (pin "1") (pinfunction "1_1") (pintype "passive"))
      (node (ref "R20") (pin "1") (pinfunction "1_1") (pintype "passive"))
      (node (ref "R21") (pin "1") (pinfunction "1_1") (pintype "passive"))
      (node (ref "R22") (pin "2") (pinfunction "2_2") (pintype "passive"))
      (node (ref "R23") (pin "1") (pinfunction "1_1") (pintype "passive"))
      (node (ref "R24") (pin "1") (pinfunction "1_1") (pintype "passive"))
      (node (ref "R29") (pin "1") (pinfunction "1_1") (pintype "passive"))
      (node (ref "R3") (pin "1") (pinfunction "1_1") (pintype "passive"))
      (node (ref "R34") (pin "1") (pinfunction "1_1") (pintype "passive"))
      (node (ref "R35") (pin "2") (pinfunction "2_2") (pintype "passive"))
      (node (ref "R4") (pin "1") (pinfunction "1_1") (pintype "passive"))
      (node (ref "R6") (pin "2") (pinfunction "2_2") (pintype "passive"))
      (node (ref "SW1") (pin "1") (pinfunction "P1_1") (pintype "passive"))
      (node (ref "SW2") (pin "1") (pinfunction "P1_1") (pintype "passive"))
      (node (ref "SW3") (pin "1") (pinfunction "P1_1") (pintype "passive"))
      (node (ref "TP2") (pin "1") (pinfunction "1_1") (pintype "passive"))
      (node (ref "U1") (pin "4") (pinfunction "GND_4") (pintype "power_in"))
      (node (ref "U3") (pin "8") (pinfunction "GND_8") (pintype "power_in"))
      (node (ref "U3") (pin "9") (pinfunction "POWERPAD_9") (pintype "power_in"))
      (node (ref "U4") (pin "2") (pinfunction "GND_2") (pintype "passive"))
      (node (ref "U4") (pin "4") (pinfunction "NC_4") (pintype "passive"))
      (node (ref "U5") (pin "2") (pinfunction "2_2") (pintype "passive"))
      (node (ref "U6") (pin "3") (pinfunction "GND_3") (pintype "passive"))
    )
    (net (code "46") (name "GSM_ADC0") (class "Default")
      (node (ref "P2") (pin "23") (pinfunction "23_23") (pintype "passive"))
      (node (ref "R28") (pin "2") (pinfunction "2_2") (pintype "passive"))
    )
    (net (code "47") (name "Net-(ANT1-ant)") (class "Default")
      (node (ref "ANT1") (pin "2") (pinfunction "ant_2") (pintype "passive"))
      (node (ref "C36") (pin "2") (pinfunction "2_2") (pintype "passive"))
      (node (ref "R30") (pin "2") (pinfunction "2_2") (pintype "passive"))
    )
    (net (code "48") (name "Net-(BT1-POS)") (class "Default")
      (node (ref "BT1") (pin "P") (pinfunction "POS_P") (pintype "passive"))
      (node (ref "D2") (pin "1") (pinfunction "1_1") (pintype "passive"))
    )
    (net (code "49") (name "Net-(C2-+)") (class "Default")
      (node (ref "C2") (pin "1") (pinfunction "+_1") (pintype "passive"))
      (node (ref "C3") (pin "2") (pinfunction "2_2") (pintype "passive"))
      (node (ref "C4") (pin "2") (pinfunction "2_2") (pintype "passive"))
      (node (ref "C5") (pin "2") (pinfunction "2_2") (pintype "passive"))
      (node (ref "D1") (pin "C") (pinfunction "C_C") (pintype "passive"))
      (node (ref "F1") (pin "2") (pinfunction "2_2") (pintype "passive"))
      (node (ref "R1") (pin "2") (pinfunction "2_2") (pintype "passive"))
      (node (ref "TP5") (pin "1") (pinfunction "1_1") (pintype "passive"))
      (node (ref "U1") (pin "3") (pinfunction "VIN_3") (pintype "input"))
    )
    (net (code "50") (name "Net-(D4-ANODE)") (class "Default")
      (node (ref "D4") (pin "1") (pinfunction "ANODE_1") (pintype "passive"))
      (node (ref "R36") (pin "2") (pinfunction "2_2") (pintype "passive"))
    )
    (net (code "51") (name "Net-(D6-CATHODE)") (class "Default")
      (node (ref "D6") (pin "2") (pinfunction "CATHODE_2") (pintype "passive"))
      (node (ref "R22") (pin "1") (pinfunction "1_1") (pintype "passive"))
    )
    (net (code "52") (name "Net-(D7-CATHODE)") (class "Default")
      (node (ref "D7") (pin "2") (pinfunction "CATHODE_2") (pintype "passive"))
      (node (ref "R14") (pin "2") (pinfunction "2_2") (pintype "passive"))
    )
    (net (code "53") (name "Net-(D8-CATHODE)") (class "Default")
      (node (ref "D8") (pin "2") (pinfunction "CATHODE_2") (pintype "passive"))
      (node (ref "R24") (pin "2") (pinfunction "2_2") (pintype "passive"))
    )
    (net (code "54") (name "Net-(D9-ANODE)") (class "Default")
      (node (ref "D9") (pin "1") (pinfunction "ANODE_1") (pintype "passive"))
      (node (ref "R27") (pin "2") (pinfunction "2_2") (pintype "passive"))
    )
    (net (code "55") (name "Net-(D10-CATHODE)") (class "Default")
      (node (ref "D10") (pin "2") (pinfunction "CATHODE_2") (pintype "passive"))
      (node (ref "R32") (pin "2") (pinfunction "2_2") (pintype "passive"))
    )
    (net (code "56") (name "Net-(D13-ANODE)") (class "Default")
      (node (ref "D13") (pin "1") (pinfunction "ANODE_1") (pintype "passive"))
      (node (ref "R37") (pin "2") (pinfunction "2_2") (pintype "passive"))
    )
    (net (code "57") (name "Net-(F1-Pad1)") (class "Default")
      (node (ref "F1") (pin "1") (pinfunction "1_1") (pintype "passive"))
      (node (ref "J1") (pin "1") (pinfunction "1_1") (pintype "passive"))
    )
    (net (code "58") (name "Net-(F2-Pad2)") (class "Default")
      (node (ref "F2") (pin "2") (pinfunction "2_2") (pintype "passive"))
      (node (ref "J2") (pin "A4B9") (pinfunction "VBUS_A4B9") (pintype "passive"))
      (node (ref "J2") (pin "B4A9") (pinfunction "VBUS_B4A9") (pintype "passive"))
    )
    (net (code "59") (name "Net-(J2-CC1)") (class "Default")
      (node (ref "J2") (pin "A5") (pinfunction "CC1_A5") (pintype "passive"))
      (node (ref "R20") (pin "2") (pinfunction "2_2") (pintype "passive"))
    )
    (net (code "60") (name "Net-(J2-CC2)") (class "Default")
      (node (ref "J2") (pin "B5") (pinfunction "CC2_B5") (pintype "passive"))
      (node (ref "R21") (pin "2") (pinfunction "2_2") (pintype "passive"))
    )
    (net (code "61") (name "Net-(J3-CLK)") (class "Default")
      (node (ref "C26") (pin "2") (pinfunction "2_2") (pintype "passive"))
      (node (ref "D5") (pin "1") (pinfunction "K_1") (pintype "passive"))
      (node (ref "J3") (pin "C3") (pinfunction "CLK_C3") (pintype "input"))
      (node (ref "R18") (pin "2") (pinfunction "2_2") (pintype "passive"))
    )
    (net (code "62") (name "Net-(J3-DATA)") (class "Default")
      (node (ref "C27") (pin "2") (pinfunction "2_2") (pintype "passive"))
      (node (ref "D5") (pin "3") (pinfunction "K_3") (pintype "passive"))
      (node (ref "J3") (pin "C7") (pinfunction "DATA_C7") (pintype "bidirectional"))
      (node (ref "R17") (pin "2") (pinfunction "2_2") (pintype "passive"))
    )
    (net (code "63") (name "Net-(J3-RST)") (class "Default")
      (node (ref "C25") (pin "2") (pinfunction "2_2") (pintype "passive"))
      (node (ref "D5") (pin "5") (pinfunction "K_5") (pintype "passive"))
      (node (ref "J3") (pin "C2") (pinfunction "RST_C2") (pintype "input"))
      (node (ref "R19") (pin "2") (pinfunction "2_2") (pintype "passive"))
    )
    (net (code "64") (name "Net-(J4-SIG)") (class "Default")
      (node (ref "C38") (pin "2") (pinfunction "2_2") (pintype "passive"))
      (node (ref "J4") (pin "1") (pinfunction "SIG_1") (pintype "passive"))
      (node (ref "R31") (pin "2") (pinfunction "2_2") (pintype "passive"))
    )
    (net (code "65") (name "Net-(J5-SP_Left_OUT)") (class "Default")
      (node (ref "C52") (pin "2") (pinfunction "2_2") (pintype "passive"))
      (node (ref "C55") (pin "2") (pinfunction "2_2") (pintype "passive"))
      (node (ref "C56") (pin "2") (pinfunction "2_2") (pintype "passive"))
      (node (ref "D11") (pin "5") (pinfunction "K_5") (pintype "passive"))
      (node (ref "J5") (pin "3") (pinfunction "SP_Right_OUT_3") (pintype "passive"))
      (node (ref "J5") (pin "4") (pinfunction "SP_Left_OUT_4") (pintype "passive"))
    )
    (net (code "66") (name "Net-(MC1-RXD)") (class "Default")
      (node (ref "MC1") (pin "18") (pinfunction "RXD_18") (pintype "passive"))
      (node (ref "R6") (pin "1") (pinfunction "1_1") (pintype "passive"))
      (node (ref "R8") (pin "2") (pinfunction "2_2") (pintype "passive"))
    )
    (net (code "67") (name "Net-(MC1-TXD)") (class "Default")
      (node (ref "MC1") (pin "17") (pinfunction "TXD_17") (pintype "passive"))
      (node (ref "R7") (pin "2") (pinfunction "2_2") (pintype "passive"))
    )
    (net (code "68") (name "Net-(MC1-VRTC)") (class "Default")
      (node (ref "D2") (pin "3") (pinfunction "3_3") (pintype "passive"))
      (node (ref "MC1") (pin "44") (pinfunction "VRTC_44") (pintype "passive"))
    )
    (net (code "69") (name "Net-(Q1-B)") (class "Default")
      (node (ref "Q1") (pin "1") (pinfunction "B_1") (pintype "passive"))
      (node (ref "R12") (pin "2") (pinfunction "2_2") (pintype "passive"))
      (node (ref "R13") (pin "1") (pinfunction "1_1") (pintype "passive"))
    )
    (net (code "70") (name "Net-(Q1-C)") (class "Default")
      (node (ref "Q1") (pin "3") (pinfunction "C_3") (pintype "passive"))
      (node (ref "R9") (pin "2") (pinfunction "2_2") (pintype "passive"))
      (node (ref "U3") (pin "2") (pinfunction "EN_2") (pintype "input"))
    )
    (net (code "71") (name "Net-(Q2-C1)") (class "Default")
      (node (ref "Q2") (pin "6") (pinfunction "C1_6") (pintype "power_in"))
      (node (ref "R32") (pin "1") (pinfunction "1_1") (pintype "passive"))
    )
    (net (code "72") (name "Net-(Q2-C2)") (class "Default")
      (node (ref "Q2") (pin "3") (pinfunction "C2_3") (pintype "power_in"))
      (node (ref "R14") (pin "1") (pinfunction "1_1") (pintype "passive"))
    )
    (net (code "73") (name "Net-(Q3-B)") (class "Default")
      (node (ref "Q3") (pin "1") (pinfunction "B_1") (pintype "passive"))
      (node (ref "R33") (pin "2") (pinfunction "2_2") (pintype "passive"))
      (node (ref "R35") (pin "1") (pinfunction "1_1") (pintype "passive"))
    )
    (net (code "74") (name "Net-(U1-BST)") (class "Default")
      (node (ref "C1") (pin "1") (pinfunction "1_1") (pintype "passive"))
      (node (ref "U1") (pin "6") (pinfunction "BST_6") (pintype "input"))
    )
    (net (code "75") (name "Net-(U1-EN)") (class "Default")
      (node (ref "R1") (pin "1") (pinfunction "1_1") (pintype "passive"))
      (node (ref "R2") (pin "2") (pinfunction "2_2") (pintype "passive"))
      (node (ref "U1") (pin "2") (pinfunction "EN_2") (pintype "input"))
    )
    (net (code "76") (name "Net-(U1-RT)") (class "Default")
      (node (ref "R3") (pin "2") (pinfunction "2_2") (pintype "passive"))
      (node (ref "U1") (pin "1") (pinfunction "RT_1") (pintype "input"))
    )
    (net (code "77") (name "Net-(U1-SS)") (class "Default")
      (node (ref "C9") (pin "2") (pinfunction "2_2") (pintype "passive"))
      (node (ref "U1") (pin "7") (pinfunction "SS_7") (pintype "input"))
    )
    (net (code "78") (name "Net-(U1-SW)") (class "Default")
      (node (ref "C1") (pin "2") (pinfunction "2_2") (pintype "passive"))
      (node (ref "L1") (pin "1") (pinfunction "1_1") (pintype "passive"))
      (node (ref "U1") (pin "5") (pinfunction "SW_5") (pintype "output"))
    )
    (net (code "79") (name "VBAT") (class "Default")
      (node (ref "C12") (pin "2") (pinfunction "2_2") (pintype "passive"))
      (node (ref "C17") (pin "1") (pinfunction "P_1") (pintype "power_in"))
      (node (ref "C18") (pin "1") (pinfunction "P_1") (pintype "power_in"))
      (node (ref "C19") (pin "2") (pinfunction "2_2") (pintype "passive"))
      (node (ref "C20") (pin "2") (pinfunction "2_2") (pintype "passive"))
      (node (ref "C21") (pin "2") (pinfunction "2_2") (pintype "passive"))
      (node (ref "C22") (pin "2") (pinfunction "2_2") (pintype "passive"))
      (node (ref "C23") (pin "1") (pinfunction "1_1") (pintype "passive"))
      (node (ref "D8") (pin "1") (pinfunction "ANODE_1") (pintype "passive"))
      (node (ref "MC1") (pin "42") (pinfunction "VBAT_42") (pintype "passive"))
      (node (ref "MC1") (pin "43") (pinfunction "VBAT_43") (pintype "passive"))
      (node (ref "R10") (pin "2") (pinfunction "2_2") (pintype "passive"))
      (node (ref "TP3") (pin "1") (pinfunction "1_1") (pintype "passive"))
      (node (ref "U3") (pin "6") (pinfunction "OUT_6") (pintype "power_in"))
    )
    (net (code "80") (name "VBUS1") (class "Default")
      (node (ref "C29") (pin "2") (pinfunction "2_2") (pintype "passive"))
      (node (ref "D6") (pin "1") (pinfunction "ANODE_1") (pintype "passive"))
      (node (ref "F2") (pin "1") (pinfunction "1_1") (pintype "passive"))
      (node (ref "U5") (pin "5") (pinfunction "5_5") (pintype "passive"))
    )
    (net (code "81") (name "VDD_EXT") (class "Default")
      (node (ref "C30") (pin "2") (pinfunction "2_2") (pintype "passive"))
      (node (ref "FB1") (pin "1") (pinfunction "1_1") (pintype "passive"))
      (node (ref "MC1") (pin "24") (pinfunction "VDD_EXT_24") (pintype "passive"))
      (node (ref "R25") (pin "2") (pinfunction "2_2") (pintype "passive"))
      (node (ref "R26") (pin "2") (pinfunction "2_2") (pintype "passive"))
    )
    (net (code "82") (name "unconnected-(D2-Pad2)") (class "Default")
      (node (ref "D2") (pin "2") (pinfunction "2_2") (pintype "passive+no_connect"))
    )
    (net (code "83") (name "unconnected-(D5-K-Pad2)") (class "Default")
      (node (ref "D5") (pin "2") (pinfunction "K_2") (pintype "passive"))
    )
    (net (code "84") (name "unconnected-(D11-K-Pad1)") (class "Default")
      (node (ref "D11") (pin "1") (pinfunction "K_1") (pintype "passive+no_connect"))
    )
    (net (code "85") (name "unconnected-(D11-K-Pad3)") (class "Default")
      (node (ref "D11") (pin "3") (pinfunction "K_3") (pintype "passive+no_connect"))
    )
    (net (code "86") (name "unconnected-(D12-K-Pad1)") (class "Default")
      (node (ref "D12") (pin "1") (pinfunction "K_1") (pintype "passive+no_connect"))
    )
    (net (code "87") (name "unconnected-(D12-K-Pad5)") (class "Default")
      (node (ref "D12") (pin "5") (pinfunction "K_5") (pintype "passive+no_connect"))
    )
    (net (code "88") (name "unconnected-(J2-SBU1-PadA8)") (class "Default")
      (node (ref "J2") (pin "A8") (pinfunction "SBU1_A8") (pintype "passive+no_connect"))
    )
    (net (code "89") (name "unconnected-(J2-SBU2-PadB8)") (class "Default")
      (node (ref "J2") (pin "B8") (pinfunction "SBU2_B8") (pintype "passive+no_connect"))
    )
    (net (code "90") (name "unconnected-(J3-VPP-PadC6)") (class "Default")
      (node (ref "J3") (pin "C6") (pinfunction "VPP_C6") (pintype "power_in+no_connect"))
    )
    (net (code "91") (name "unconnected-(J5-SP_Left_IN-Pad5)") (class "Default")
      (node (ref "J5") (pin "5") (pinfunction "SP_Left_IN_5") (pintype "passive+no_connect"))
    )
    (net (code "92") (name "unconnected-(J5-SP_Right_IN-Pad6)") (class "Default")
      (node (ref "J5") (pin "6") (pinfunction "SP_Right_IN_6") (pintype "passive+no_connect"))
    )
    (net (code "93") (name "unconnected-(S1-Pad1)") (class "Default")
      (node (ref "S1") (pin "1") (pinfunction "1_1") (pintype "power_in+no_connect"))
    )
    (net (code "94") (name "unconnected-(S2-Pad1)") (class "Default")
      (node (ref "S2") (pin "1") (pinfunction "1_1") (pintype "power_in+no_connect"))
    )
    (net (code "95") (name "unconnected-(S3-Pad1)") (class "Default")
      (node (ref "S3") (pin "1") (pinfunction "1_1") (pintype "power_in+no_connect"))
    )
    (net (code "96") (name "unconnected-(S4-Pad1)") (class "Default")
      (node (ref "S4") (pin "1") (pinfunction "1_1") (pintype "power_in+no_connect"))
    )
    (net (code "97") (name "unconnected-(U3-NC_1-Pad1)") (class "Default")
      (node (ref "U3") (pin "1") (pinfunction "NC_1_1") (pintype "passive+no_connect"))
    )
    (net (code "98") (name "unconnected-(U3-NC_4-Pad4)") (class "Default")
      (node (ref "U3") (pin "4") (pinfunction "NC_4_4") (pintype "passive+no_connect"))
    )
    (net (code "99") (name "unconnected-(U3-NC_5-Pad5)") (class "Default")
      (node (ref "U3") (pin "5") (pinfunction "NC_5_5") (pintype "passive+no_connect"))
    )
    (net (code "100") (name "unconnected-(U5-Pad3)") (class "Default")
      (node (ref "U5") (pin "3") (pinfunction "3_3") (pintype "passive+no_connect"))
    )
    (net (code "101") (name "unconnected-(U5-Pad4)") (class "Default")
      (node (ref "U5") (pin "4") (pinfunction "4_4") (pintype "passive+no_connect"))
    )
    (net (code "102") (name "unconnected-(U6-RTS-Pad4)") (class "Default")
      (node (ref "U6") (pin "4") (pinfunction "RTS_4") (pintype "passive+no_connect"))
    )
  )
)
